# PCB_V3.net
KiCad netlist of a schematic drawn in EAGLE
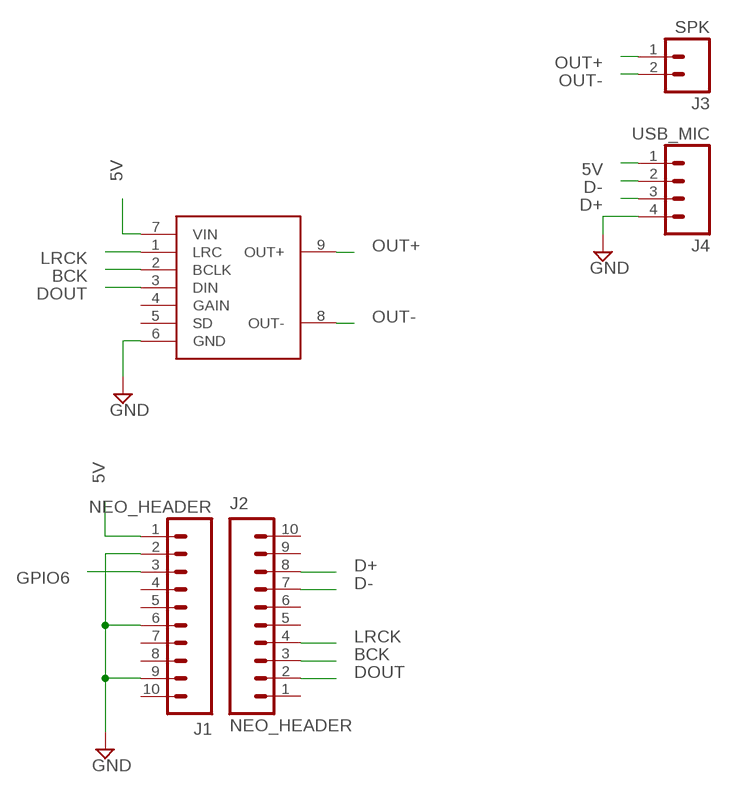
[diagram p0: schematic, sheet 1]

(export (version "E")
  (design (tool "Eeschema 10.0.6"))
  (components
    (comp (ref "J1")
      (value "NEO_HEADER")
      (footprint "eagle-import:1X10_NO_SILK")
      (libsource (lib "eagle-import") (part "M10NO_SILK_PTH_FEMALE"))
    )
    (comp (ref "J2")
      (value "NEO_HEADER")
      (footprint "eagle-import:1X10_NO_SILK")
      (libsource (lib "eagle-import") (part "M10NO_SILK_PTH_FEMALE"))
    )
    (comp (ref "J3")
      (value "SPK")
      (footprint "eagle-import:1X02_NO_SILK")
      (libsource (lib "eagle-import") (part "M021X02_NO_SILK"))
    )
    (comp (ref "J4")
      (value "USB_MIC")
      (footprint "eagle-import:1X04_NO_SILK")
      (libsource (lib "eagle-import") (part "M041X04_NO_SILK"))
    )
    (comp (ref "U$1")
      (value "I2S_BREAKOUT")
      (footprint "eagle-import:I2S_BREAKOUT")
      (libsource (lib "eagle-import") (part "I2S_BREAKOUT"))
    )
  )
  (nets
    (net (code "1") (name "/5V") (class "Default")
      (node (ref "J1") (pin "1") (pinfunction "1_1") (pintype "passive"))
      (node (ref "J4") (pin "1") (pinfunction "1_1") (pintype "passive"))
      (node (ref "U$1") (pin "7") (pinfunction "VIN_7") (pintype "bidirectional"))
    )
    (net (code "2") (name "/BCK") (class "Default")
      (node (ref "J2") (pin "3") (pinfunction "3_3") (pintype "passive"))
      (node (ref "U$1") (pin "2") (pinfunction "BCLK_2") (pintype "bidirectional"))
    )
    (net (code "3") (name "/D+") (class "Default")
      (node (ref "J2") (pin "8") (pinfunction "8_8") (pintype "passive"))
      (node (ref "J4") (pin "3") (pinfunction "3_3") (pintype "passive"))
    )
    (net (code "4") (name "/D-") (class "Default")
      (node (ref "J2") (pin "7") (pinfunction "7_7") (pintype "passive"))
      (node (ref "J4") (pin "2") (pinfunction "2_2") (pintype "passive"))
    )
    (net (code "5") (name "/DOUT") (class "Default")
      (node (ref "J2") (pin "2") (pinfunction "2_2") (pintype "passive"))
      (node (ref "U$1") (pin "3") (pinfunction "DIN_3") (pintype "bidirectional"))
    )
    (net (code "6") (name "/GPIO6") (class "Default")
      (node (ref "J1") (pin "3") (pinfunction "3_3") (pintype "passive"))
    )
    (net (code "7") (name "/LRCK") (class "Default")
      (node (ref "J2") (pin "4") (pinfunction "4_4") (pintype "passive"))
      (node (ref "U$1") (pin "1") (pinfunction "LRC_1") (pintype "bidirectional"))
    )
    (net (code "8") (name "/OUT+") (class "Default")
      (node (ref "J3") (pin "1") (pinfunction "1_1") (pintype "passive"))
      (node (ref "U$1") (pin "9") (pinfunction "OUT+_9") (pintype "bidirectional"))
    )
    (net (code "9") (name "/OUT-") (class "Default")
      (node (ref "J3") (pin "2") (pinfunction "2_2") (pintype "passive"))
      (node (ref "U$1") (pin "8") (pinfunction "OUT-_8") (pintype "bidirectional"))
    )
    (net (code "10") (name "GND") (class "Default")
      (node (ref "J1") (pin "2") (pinfunction "2_2") (pintype "passive"))
      (node (ref "J1") (pin "6") (pinfunction "6_6") (pintype "passive"))
      (node (ref "J1") (pin "9") (pinfunction "9_9") (pintype "passive"))
      (node (ref "J4") (pin "4") (pinfunction "4_4") (pintype "passive"))
      (node (ref "U$1") (pin "6") (pinfunction "GND_6") (pintype "bidirectional"))
    )
    (net (code "11") (name "unconnected-(J1-Pad4)") (class "Default")
      (node (ref "J1") (pin "4") (pinfunction "4_4") (pintype "passive"))
    )
    (net (code "12") (name "unconnected-(J1-Pad5)") (class "Default")
      (node (ref "J1") (pin "5") (pinfunction "5_5") (pintype "passive"))
    )
    (net (code "13") (name "unconnected-(J1-Pad7)") (class "Default")
      (node (ref "J1") (pin "7") (pinfunction "7_7") (pintype "passive"))
    )
    (net (code "14") (name "unconnected-(J1-Pad8)") (class "Default")
      (node (ref "J1") (pin "8") (pinfunction "8_8") (pintype "passive"))
    )
    (net (code "15") (name "unconnected-(J1-Pad10)") (class "Default")
      (node (ref "J1") (pin "10") (pinfunction "10_10") (pintype "passive"))
    )
    (net (code "16") (name "unconnected-(J2-Pad1)") (class "Default")
      (node (ref "J2") (pin "1") (pinfunction "1_1") (pintype "passive"))
    )
    (net (code "17") (name "unconnected-(J2-Pad5)") (class "Default")
      (node (ref "J2") (pin "5") (pinfunction "5_5") (pintype "passive"))
    )
    (net (code "18") (name "unconnected-(J2-Pad6)") (class "Default")
      (node (ref "J2") (pin "6") (pinfunction "6_6") (pintype "passive"))
    )
    (net (code "19") (name "unconnected-(J2-Pad9)") (class "Default")
      (node (ref "J2") (pin "9") (pinfunction "9_9") (pintype "passive"))
    )
    (net (code "20") (name "unconnected-(J2-Pad10)") (class "Default")
      (node (ref "J2") (pin "10") (pinfunction "10_10") (pintype "passive"))
    )
    (net (code "21") (name "unconnected-(U$1-GAIN-Pad4)") (class "Default")
      (node (ref "U$1") (pin "4") (pinfunction "GAIN_4") (pintype "bidirectional"))
    )
    (net (code "22") (name "unconnected-(U$1-SD-Pad5)") (class "Default")
      (node (ref "U$1") (pin "5") (pinfunction "SD_5") (pintype "bidirectional"))
    )
  )
)
